# Reflowduino32_v1.net
KiCad netlist of a schematic drawn in EAGLE
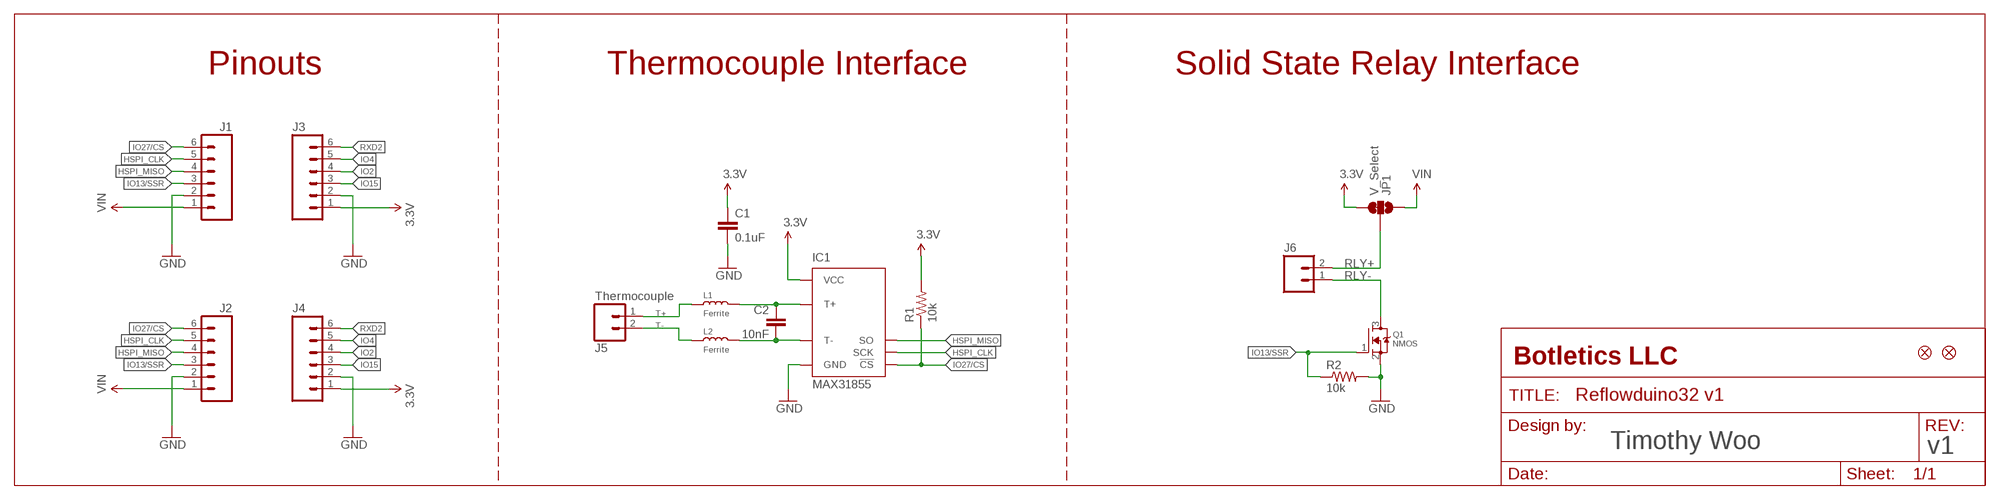
[diagram p0: schematic, sheet 1]

(export (version "E")
  (design (tool "Eeschema 10.0.6"))
  (components
    (comp (ref "C1")
      (value "0.1uF")
      (footprint "eagle-import:0603-CAP-MARKED")
      (libsource (lib "eagle-import") (part "CAPMARKED-0603"))
    )
    (comp (ref "C2")
      (value "10nF")
      (footprint "eagle-import:0603-CAP-MARKED")
      (libsource (lib "eagle-import") (part "CAPMARKED-0603"))
    )
    (comp (ref "FID1")
      (value "FIDUCIAL")
      (footprint "eagle-import:FIDUCIAL_1MM")
      (libsource (lib "eagle-import") (part "FIDUCIAL"))
    )
    (comp (ref "FID2")
      (value "FIDUCIAL")
      (footprint "eagle-import:FIDUCIAL_1MM")
      (libsource (lib "eagle-import") (part "FIDUCIAL"))
    )
    (comp (ref "IC1")
      (value "MAX31855")
      (footprint "eagle-import:MAX31855_SOIC8")
      (libsource (lib "eagle-import") (part "MAX31855"))
    )
    (comp (ref "J1")
      (value "M06SILK_PTH")
      (footprint "eagle-import:1X06")
      (libsource (lib "eagle-import") (part "M06SILK_PTH"))
    )
    (comp (ref "J2")
      (value "M06NO_SILK_FEMALE_PTH")
      (footprint "eagle-import:1X06_NO_SILK")
      (libsource (lib "eagle-import") (part "M06NO_SILK_FEMALE_PTH"))
    )
    (comp (ref "J3")
      (value "M06SILK_PTH")
      (footprint "eagle-import:1X06")
      (libsource (lib "eagle-import") (part "M06SILK_PTH"))
    )
    (comp (ref "J4")
      (value "M06NO_SILK_FEMALE_PTH")
      (footprint "eagle-import:1X06_NO_SILK")
      (libsource (lib "eagle-import") (part "M06NO_SILK_FEMALE_PTH"))
    )
    (comp (ref "J5")
      (value "Thermocouple")
      (footprint "eagle-import:SCREWTERMINAL-3.5MM-2")
      (libsource (lib "eagle-import") (part "M023.5MM"))
    )
    (comp (ref "J6")
      (value "M023.5MM")
      (footprint "eagle-import:SCREWTERMINAL-3.5MM-2")
      (libsource (lib "eagle-import") (part "M023.5MM"))
    )
    (comp (ref "JP1")
      (value "V_Select")
      (footprint "eagle-import:SMT-JUMPER_3_1-NC_TRACE_SILK")
      (libsource (lib "eagle-import") (part "JUMPER-SMT_3_1-NC_TRACE_SILK"))
    )
    (comp (ref "L1")
      (value "Ferrite")
      (footprint "eagle-import:L0603")
      (libsource (lib "eagle-import") (part "SMD-FERRITE-BEAD-2500R-50MA(0603)"))
    )
    (comp (ref "L2")
      (value "Ferrite")
      (footprint "eagle-import:L0603")
      (libsource (lib "eagle-import") (part "SMD-FERRITE-BEAD-2500R-50MA(0603)"))
    )
    (comp (ref "Q1")
      (value "NMOS")
      (footprint "eagle-import:SOT23-3")
      (libsource (lib "eagle-import") (part "MOSFET-NGENERIC"))
    )
    (comp (ref "R1")
      (value "10k")
      (footprint "eagle-import:0603-RES-MARKED")
      (libsource (lib "eagle-import") (part "RESISTORMARKED-0603"))
    )
    (comp (ref "R2")
      (value "10k")
      (footprint "eagle-import:0603-RES-MARKED")
      (libsource (lib "eagle-import") (part "RESISTORMARKED-0603"))
    )
  )
  (nets
    (net (code "1") (name "/RLY+") (class "Default")
      (node (ref "J6") (pin "2") (pinfunction "2_2") (pintype "passive"))
      (node (ref "JP1") (pin "2") (pinfunction "2_2") (pintype "passive"))
    )
    (net (code "2") (name "/RLY-") (class "Default")
      (node (ref "J6") (pin "1") (pinfunction "1_1") (pintype "passive"))
      (node (ref "Q1") (pin "3") (pinfunction "D_3") (pintype "bidirectional"))
    )
    (net (code "3") (name "/T+") (class "Default")
      (node (ref "J5") (pin "1") (pinfunction "1_1") (pintype "passive"))
      (node (ref "L1") (pin "1") (pinfunction "1_1") (pintype "passive"))
    )
    (net (code "4") (name "/T-") (class "Default")
      (node (ref "J5") (pin "2") (pinfunction "2_2") (pintype "passive"))
      (node (ref "L2") (pin "1") (pinfunction "1_1") (pintype "passive"))
    )
    (net (code "5") (name "3.3V") (class "Default")
      (node (ref "C1") (pin "1") (pinfunction "1_1") (pintype "passive"))
      (node (ref "IC1") (pin "4") (pinfunction "VCC_4") (pintype "power_in"))
      (node (ref "J3") (pin "1") (pinfunction "1_1") (pintype "passive"))
      (node (ref "J4") (pin "1") (pinfunction "1_1") (pintype "passive"))
      (node (ref "JP1") (pin "3") (pinfunction "3_3") (pintype "passive"))
      (node (ref "R1") (pin "2") (pinfunction "2_2") (pintype "passive"))
    )
    (net (code "6") (name "GND") (class "Default")
      (node (ref "C1") (pin "2") (pinfunction "2_2") (pintype "passive"))
      (node (ref "IC1") (pin "1") (pinfunction "GND_1") (pintype "power_in"))
      (node (ref "J1") (pin "2") (pinfunction "2_2") (pintype "passive"))
      (node (ref "J2") (pin "2") (pinfunction "2_2") (pintype "passive"))
      (node (ref "J3") (pin "2") (pinfunction "2_2") (pintype "passive"))
      (node (ref "J4") (pin "2") (pinfunction "2_2") (pintype "passive"))
      (node (ref "Q1") (pin "2") (pinfunction "S_2") (pintype "bidirectional"))
      (node (ref "R2") (pin "2") (pinfunction "2_2") (pintype "passive"))
    )
    (net (code "7") (name "HSPI_CLK") (class "Default")
      (node (ref "IC1") (pin "5") (pinfunction "SCK_5") (pintype "bidirectional"))
      (node (ref "J1") (pin "5") (pinfunction "5_5") (pintype "passive"))
      (node (ref "J2") (pin "5") (pinfunction "5_5") (pintype "passive"))
    )
    (net (code "8") (name "HSPI_MISO") (class "Default")
      (node (ref "IC1") (pin "7") (pinfunction "SO_7") (pintype "bidirectional"))
      (node (ref "J1") (pin "4") (pinfunction "4_4") (pintype "passive"))
      (node (ref "J2") (pin "4") (pinfunction "4_4") (pintype "passive"))
    )
    (net (code "9") (name "IO2") (class "Default")
      (node (ref "J3") (pin "4") (pinfunction "4_4") (pintype "passive"))
      (node (ref "J4") (pin "4") (pinfunction "4_4") (pintype "passive"))
    )
    (net (code "10") (name "IO4") (class "Default")
      (node (ref "J3") (pin "5") (pinfunction "5_5") (pintype "passive"))
      (node (ref "J4") (pin "5") (pinfunction "5_5") (pintype "passive"))
    )
    (net (code "11") (name "IO13{slash}SSR") (class "Default")
      (node (ref "J1") (pin "3") (pinfunction "3_3") (pintype "passive"))
      (node (ref "J2") (pin "3") (pinfunction "3_3") (pintype "passive"))
      (node (ref "Q1") (pin "1") (pinfunction "G_1") (pintype "bidirectional"))
      (node (ref "R2") (pin "1") (pinfunction "1_1") (pintype "passive"))
    )
    (net (code "12") (name "IO15") (class "Default")
      (node (ref "J3") (pin "3") (pinfunction "3_3") (pintype "passive"))
      (node (ref "J4") (pin "3") (pinfunction "3_3") (pintype "passive"))
    )
    (net (code "13") (name "IO27{slash}CS") (class "Default")
      (node (ref "IC1") (pin "6") (pinfunction "~{CS}_6") (pintype "bidirectional"))
      (node (ref "J1") (pin "6") (pinfunction "6_6") (pintype "passive"))
      (node (ref "J2") (pin "6") (pinfunction "6_6") (pintype "passive"))
      (node (ref "R1") (pin "1") (pinfunction "1_1") (pintype "passive"))
    )
    (net (code "14") (name "Net-(IC1-T+)") (class "Default")
      (node (ref "C2") (pin "1") (pinfunction "1_1") (pintype "passive"))
      (node (ref "IC1") (pin "3") (pinfunction "T+_3") (pintype "bidirectional"))
      (node (ref "L1") (pin "2") (pinfunction "2_2") (pintype "passive"))
    )
    (net (code "15") (name "Net-(IC1-T-)") (class "Default")
      (node (ref "C2") (pin "2") (pinfunction "2_2") (pintype "passive"))
      (node (ref "IC1") (pin "2") (pinfunction "T-_2") (pintype "bidirectional"))
      (node (ref "L2") (pin "2") (pinfunction "2_2") (pintype "passive"))
    )
    (net (code "16") (name "RXD2") (class "Default")
      (node (ref "J3") (pin "6") (pinfunction "6_6") (pintype "passive"))
      (node (ref "J4") (pin "6") (pinfunction "6_6") (pintype "passive"))
    )
    (net (code "17") (name "VIN") (class "Default")
      (node (ref "J1") (pin "1") (pinfunction "1_1") (pintype "passive"))
      (node (ref "J2") (pin "1") (pinfunction "1_1") (pintype "passive"))
      (node (ref "JP1") (pin "1") (pinfunction "1_1") (pintype "passive"))
    )
  )
)
